# tsmp6000_breakout.net
KiCad netlist of a schematic drawn in EAGLE
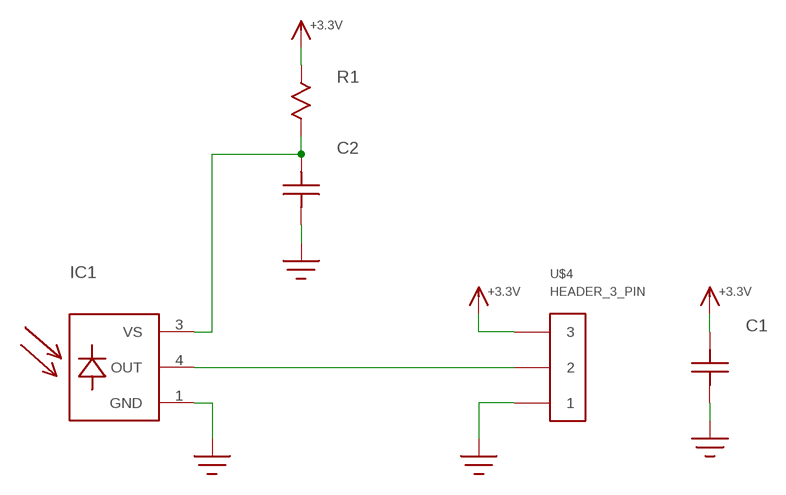
[diagram p0: schematic, sheet 1]

(export (version "E")
  (design (tool "Eeschema 10.0.6"))
  (components
    (comp (ref "C1")
      (value "C1206")
      (footprint "eagle-import:1206")
      (libsource (lib "eagle-import") (part "C1206"))
    )
    (comp (ref "C2")
      (value "C0805")
      (footprint "eagle-import:0805")
      (libsource (lib "eagle-import") (part "C0805"))
    )
    (comp (ref "IC1")
      (value "TSMP6000")
      (footprint "eagle-import:TSMP6000")
      (libsource (lib "eagle-import") (part "TSMP6000"))
    )
    (comp (ref "R1")
      (value "R0805")
      (footprint "eagle-import:R0805")
      (libsource (lib "eagle-import") (part "R0805"))
    )
    (comp (ref "U$4")
      (value "HEADER_3_PIN")
      (footprint "eagle-import:HEADER_3_PIN")
      (libsource (lib "eagle-import") (part "HEADER_3_PIN"))
    )
  )
  (nets
    (net (code "1") (name "+3.3V") (class "Default")
      (node (ref "C1") (pin "P$2") (pinfunction "P$2_P$2") (pintype "bidirectional"))
      (node (ref "R1") (pin "P$1") (pinfunction "P$3_P$1") (pintype "bidirectional"))
      (node (ref "U$4") (pin "3") (pinfunction "3_3") (pintype "bidirectional"))
    )
    (net (code "2") (name "GND") (class "Default")
      (node (ref "C1") (pin "P$1") (pinfunction "P$1_P$1") (pintype "bidirectional"))
      (node (ref "C2") (pin "P$1") (pinfunction "P$1_P$1") (pintype "bidirectional"))
      (node (ref "IC1") (pin "1") (pinfunction "GND_1") (pintype "bidirectional"))
      (node (ref "U$4") (pin "1") (pinfunction "1_1") (pintype "bidirectional"))
    )
    (net (code "3") (name "Net-(IC1-OUT)") (class "Default")
      (node (ref "IC1") (pin "4") (pinfunction "OUT_4") (pintype "bidirectional"))
      (node (ref "U$4") (pin "2") (pinfunction "2_2") (pintype "bidirectional"))
    )
    (net (code "4") (name "Net-(IC1-VS)") (class "Default")
      (node (ref "C2") (pin "P$2") (pinfunction "P$2_P$2") (pintype "bidirectional"))
      (node (ref "IC1") (pin "3") (pinfunction "VS_3") (pintype "bidirectional"))
      (node (ref "R1") (pin "P$2") (pinfunction "P$4_P$2") (pintype "bidirectional"))
    )
  )
)
